# PIC32MK.net
KiCad netlist of a schematic drawn in Altium Designer
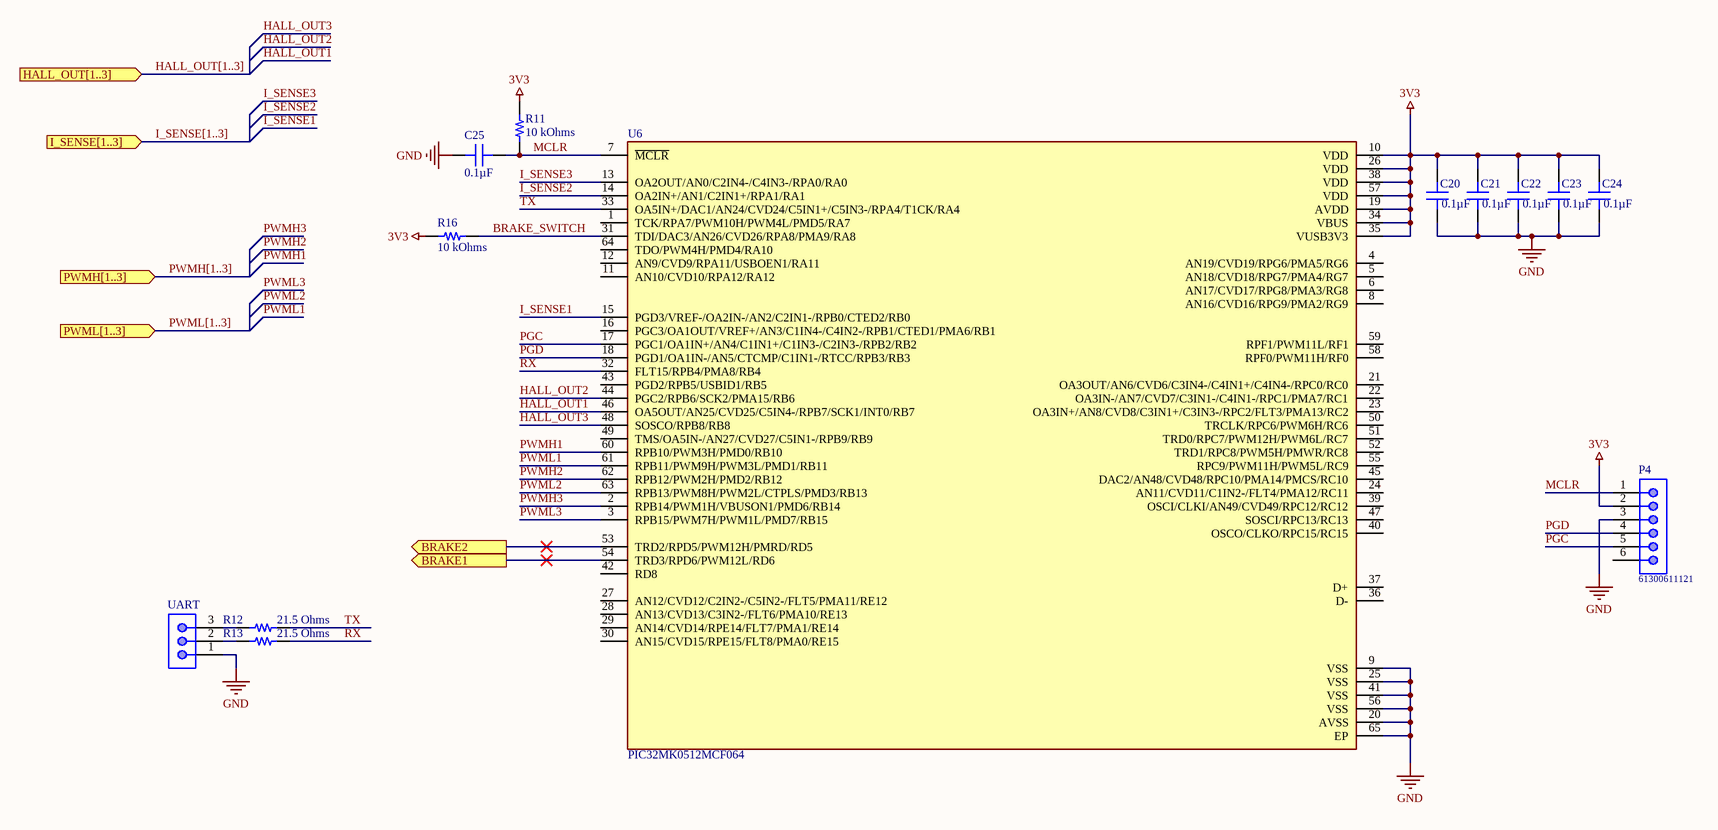
[diagram p0: PIC32MK.SchDoc]

(export (version "E")
  (design (tool "Eeschema 10.0.6"))
  (components
    (comp (ref "C20")
      (value "0.1µF")
      (footprint "CAP 0603_1608")
      (description "CAP CER 0.1UF 100V 0603 EPOXY")
      (fields
        (field (name "PART NUMBER") "GCG188R92A104KA03D")
        (field (name "MANUFACTURER") "Murata Electronics")
      )
      (libsource (lib "Celestial Altium Library - altium_library") (part "Capacitor"))
    )
    (comp (ref "C21")
      (value "0.1µF")
      (footprint "CAP 0603_1608")
      (description "CAP CER 0.1UF 100V 0603 EPOXY")
      (fields
        (field (name "PART NUMBER") "GCG188R92A104KA03D")
        (field (name "MANUFACTURER") "Murata Electronics")
      )
      (libsource (lib "Celestial Altium Library - altium_library") (part "Capacitor"))
    )
    (comp (ref "C22")
      (value "0.1µF")
      (footprint "CAP 0603_1608")
      (description "CAP CER 0.1UF 100V 0603 EPOXY")
      (fields
        (field (name "PART NUMBER") "GCG188R92A104KA03D")
        (field (name "MANUFACTURER") "Murata Electronics")
      )
      (libsource (lib "Celestial Altium Library - altium_library") (part "Capacitor"))
    )
    (comp (ref "C23")
      (value "0.1µF")
      (footprint "CAP 0603_1608")
      (description "CAP CER 0.1UF 100V 0603 EPOXY")
      (fields
        (field (name "PART NUMBER") "GCG188R92A104KA03D")
        (field (name "MANUFACTURER") "Murata Electronics")
      )
      (libsource (lib "Celestial Altium Library - altium_library") (part "Capacitor"))
    )
    (comp (ref "C24")
      (value "0.1µF")
      (footprint "CAP 0603_1608")
      (description "CAP CER 0.1UF 100V 0603 EPOXY")
      (fields
        (field (name "PART NUMBER") "GCG188R92A104KA03D")
        (field (name "MANUFACTURER") "Murata Electronics")
      )
      (libsource (lib "Celestial Altium Library - altium_library") (part "Capacitor"))
    )
    (comp (ref "C25")
      (value "0.1µF")
      (footprint "CAP 0603_1608")
      (description "CAP CER 0.1UF 100V 0603 EPOXY")
      (fields
        (field (name "PART NUMBER") "GCG188R92A104KA03D")
        (field (name "MANUFACTURER") "Murata Electronics")
      )
      (libsource (lib "Celestial Altium Library - altium_library") (part "Capacitor"))
    )
    (comp (ref "P4")
      (value "61300611121")
      (footprint "61300611121")
      (description "WR-PHD Pin Header, THT, pitch 2.54mm, Single Row, Vertical, 6p")
      (fields (field (name "MANUFACTURER") "Wurth Elektronik"))
      (libsource (lib "Altium_WR-PHD") (part "61300611121"))
    )
    (comp (ref "R11")
      (value "10 kOhms")
      (footprint "RES 0603_1608")
      (description "RES 10K OHM 0.1% 1/16W 0603")
      (fields
        (field (name "PART NUMBER") "RNCS0603BKE10K0")
        (field (name "MANUFACTURER") "Stackpole Electronics Inc")
      )
      (libsource (lib "Celestial Altium Library - altium_library") (part "Resistor"))
    )
    (comp (ref "R12")
      (value "21.5 Ohms")
      (footprint "RES 0603_1608")
      (description "RES SMD 21.5 OHM 1% 1/10W 0603")
      (fields
        (field (name "PART NUMBER") "ERJ-3EKF21R5V")
        (field (name "MANUFACTURER") "Panasonic Electronic Components")
      )
      (libsource (lib "Celestial Altium Library - altium_library") (part "Resistor"))
    )
    (comp (ref "R13")
      (value "21.5 Ohms")
      (footprint "RES 0603_1608")
      (description "RES SMD 21.5 OHM 1% 1/10W 0603")
      (fields
        (field (name "PART NUMBER") "ERJ-3EKF21R5V")
        (field (name "MANUFACTURER") "Panasonic Electronic Components")
      )
      (libsource (lib "Celestial Altium Library - altium_library") (part "Resistor"))
    )
    (comp (ref "R16")
      (value "10 kOhms")
      (footprint "RES 0603_1608")
      (description "RES 10K OHM 0.1% 1/16W 0603")
      (fields
        (field (name "PART NUMBER") "RNCS0603BKE10K0")
        (field (name "MANUFACTURER") "Stackpole Electronics Inc")
      )
      (libsource (lib "Celestial Altium Library - altium_library") (part "Resistor"))
    )
    (comp (ref "U6")
      (value "PIC32MK0512MCF064")
      (footprint "QFN50P900X900X100-65N")
      (description "PIC32MK Microcontroller IC 32-Bit 120MHz 1MB _1M x 8_ FLASH 64-TQFP _10x10_")
      (fields
        (field (name "MP") "PIC32MK1024MCF064-I/PT")
        (field (name "DIGI-KEY_PART_NUMBER") "PIC32MK1024MCF064-I/PT-ND")
      )
      (libsource (lib "IC") (part "PIC32MK0512MCF064"))
    )
    (comp (ref "UART")
      (value "3 pin 2mm JST Male")
      (footprint "3pin - 2mm header")
      (libsource (lib "IC") (part "3 pin 2mm JST Male"))
    )
  )
  (nets
    (net (code "1") (name "/BRAKE1") (class "Default")
      (node (ref "U6") (pin "54") (pinfunction "TRD3/RPD6/PWM12L/RD6_54") (pintype "passive"))
    )
    (net (code "2") (name "/BRAKE2") (class "Default")
      (node (ref "U6") (pin "53") (pinfunction "TRD2/RPD5/PWM12H/PMRD/RD5_53") (pintype "passive"))
    )
    (net (code "3") (name "/BRAKE_SWITCH") (class "Default")
      (node (ref "R16") (pin "1") (pinfunction "1_1") (pintype "passive"))
      (node (ref "U6") (pin "31") (pinfunction "TDI/DAC3/AN26/CVD26/RPA8/PMA9/RA8_31") (pintype "passive"))
    )
    (net (code "4") (name "/HALL_OUT1") (class "Default")
      (node (ref "U6") (pin "46") (pinfunction "OA5OUT/AN25/CVD25/C5IN4-/RPB7/SCK1/INT0/RB7_46") (pintype "passive"))
    )
    (net (code "5") (name "/HALL_OUT2") (class "Default")
      (node (ref "U6") (pin "44") (pinfunction "PGC2/RPB6/SCK2/PMA15/RB6_44") (pintype "passive"))
    )
    (net (code "6") (name "/HALL_OUT3") (class "Default")
      (node (ref "U6") (pin "48") (pinfunction "SOSCO/RPB8/RB8_48") (pintype "passive"))
    )
    (net (code "8") (name "/I_SENSE1") (class "Default")
      (node (ref "U6") (pin "15") (pinfunction "PGD3/VREF-/OA2IN-/AN2/C2IN1-/RPB0/CTED2/RB0_15") (pintype "passive"))
    )
    (net (code "9") (name "/I_SENSE2") (class "Default")
      (node (ref "U6") (pin "14") (pinfunction "OA2IN+/AN1/C2IN1+/RPA1/RA1_14") (pintype "passive"))
    )
    (net (code "10") (name "/I_SENSE3") (class "Default")
      (node (ref "U6") (pin "13") (pinfunction "OA2OUT/AN0/C2IN4-/C4IN3-/RPA0/RA0_13") (pintype "passive"))
    )
    (net (code "12") (name "/MCLR") (class "Default")
      (node (ref "C25") (pin "1") (pinfunction "1_1") (pintype "passive"))
      (node (ref "P4") (pin "1") (pinfunction "1_1") (pintype "passive"))
      (node (ref "R11") (pin "1") (pinfunction "1_1") (pintype "passive"))
      (node (ref "U6") (pin "7") (pinfunction "~{MCLR}_7") (pintype "passive"))
    )
    (net (code "13") (name "/PGC") (class "Default")
      (node (ref "P4") (pin "5") (pinfunction "5_5") (pintype "passive"))
      (node (ref "U6") (pin "17") (pinfunction "PGC1/OA1IN+/AN4/C1IN1+/C1IN3-/C2IN3-/RPB2/RB2_17") (pintype "passive"))
    )
    (net (code "14") (name "/PGD") (class "Default")
      (node (ref "P4") (pin "4") (pinfunction "4_4") (pintype "passive"))
      (node (ref "U6") (pin "18") (pinfunction "PGD1/OA1IN-/AN5/CTCMP/C1IN1-/RTCC/RPB3/RB3_18") (pintype "passive"))
    )
    (net (code "15") (name "/PWMH1") (class "Default")
      (node (ref "U6") (pin "60") (pinfunction "RPB10/PWM3H/PMD0/RB10_60") (pintype "passive"))
    )
    (net (code "16") (name "/PWMH2") (class "Default")
      (node (ref "U6") (pin "62") (pinfunction "RPB12/PWM2H/PMD2/RB12_62") (pintype "passive"))
    )
    (net (code "17") (name "/PWMH3") (class "Default")
      (node (ref "U6") (pin "2") (pinfunction "RPB14/PWM1H/VBUSON1/PMD6/RB14_2") (pintype "passive"))
    )
    (net (code "19") (name "/PWML1") (class "Default")
      (node (ref "U6") (pin "61") (pinfunction "RPB11/PWM9H/PWM3L/PMD1/RB11_61") (pintype "passive"))
    )
    (net (code "20") (name "/PWML2") (class "Default")
      (node (ref "U6") (pin "63") (pinfunction "RPB13/PWM8H/PWM2L/CTPLS/PMD3/RB13_63") (pintype "passive"))
    )
    (net (code "21") (name "/PWML3") (class "Default")
      (node (ref "U6") (pin "3") (pinfunction "RPB15/PWM7H/PWM1L/PMD7/RB15_3") (pintype "passive"))
    )
    (net (code "23") (name "/RX") (class "Default")
      (node (ref "R13") (pin "2") (pinfunction "2_2") (pintype "passive"))
      (node (ref "U6") (pin "32") (pinfunction "FLT15/RPB4/PMA8/RB4_32") (pintype "passive"))
    )
    (net (code "24") (name "/TX") (class "Default")
      (node (ref "R12") (pin "2") (pinfunction "2_2") (pintype "passive"))
      (node (ref "U6") (pin "33") (pinfunction "OA5IN+/DAC1/AN24/CVD24/C5IN1+/C5IN3-/RPA4/T1CK/RA4_33") (pintype "passive"))
    )
    (net (code "25") (name "3V3") (class "Default")
      (node (ref "C20") (pin "1") (pinfunction "1_1") (pintype "passive"))
      (node (ref "C21") (pin "1") (pinfunction "1_1") (pintype "passive"))
      (node (ref "C22") (pin "1") (pinfunction "1_1") (pintype "passive"))
      (node (ref "C23") (pin "1") (pinfunction "1_1") (pintype "passive"))
      (node (ref "C24") (pin "1") (pinfunction "1_1") (pintype "passive"))
      (node (ref "P4") (pin "2") (pinfunction "2_2") (pintype "passive"))
      (node (ref "R11") (pin "2") (pinfunction "2_2") (pintype "passive"))
      (node (ref "R16") (pin "2") (pinfunction "2_2") (pintype "passive"))
      (node (ref "U6") (pin "10") (pinfunction "VDD_10") (pintype "power_in"))
      (node (ref "U6") (pin "19") (pinfunction "AVDD_19") (pintype "power_in"))
      (node (ref "U6") (pin "26") (pinfunction "VDD_26") (pintype "power_in"))
      (node (ref "U6") (pin "34") (pinfunction "VBUS_34") (pintype "power_in"))
      (node (ref "U6") (pin "35") (pinfunction "VUSB3V3_35") (pintype "passive"))
      (node (ref "U6") (pin "38") (pinfunction "VDD_38") (pintype "power_in"))
      (node (ref "U6") (pin "57") (pinfunction "VDD_57") (pintype "power_in"))
    )
    (net (code "26") (name "GND") (class "Default")
      (node (ref "C20") (pin "2") (pinfunction "2_2") (pintype "passive"))
      (node (ref "C21") (pin "2") (pinfunction "2_2") (pintype "passive"))
      (node (ref "C22") (pin "2") (pinfunction "2_2") (pintype "passive"))
      (node (ref "C23") (pin "2") (pinfunction "2_2") (pintype "passive"))
      (node (ref "C24") (pin "2") (pinfunction "2_2") (pintype "passive"))
      (node (ref "C25") (pin "2") (pinfunction "2_2") (pintype "passive"))
      (node (ref "P4") (pin "3") (pinfunction "3_3") (pintype "passive"))
      (node (ref "U6") (pin "20") (pinfunction "AVSS_20") (pintype "power_in"))
      (node (ref "U6") (pin "25") (pinfunction "VSS_25") (pintype "power_in"))
      (node (ref "U6") (pin "41") (pinfunction "VSS_41") (pintype "power_in"))
      (node (ref "U6") (pin "56") (pinfunction "VSS_56") (pintype "power_in"))
      (node (ref "U6") (pin "65") (pinfunction "EP_65") (pintype "power_in"))
      (node (ref "U6") (pin "9") (pinfunction "VSS_9") (pintype "power_in"))
      (node (ref "UART") (pin "1") (pinfunction "1_1") (pintype "passive"))
    )
    (net (code "27") (name "Net-(R12-Pad1)") (class "Default")
      (node (ref "R12") (pin "1") (pinfunction "1_1") (pintype "passive"))
      (node (ref "UART") (pin "3") (pinfunction "3_3") (pintype "passive"))
    )
    (net (code "28") (name "Net-(R13-Pad1)") (class "Default")
      (node (ref "R13") (pin "1") (pinfunction "1_1") (pintype "passive"))
      (node (ref "UART") (pin "2") (pinfunction "2_2") (pintype "passive"))
    )
    (net (code "29") (name "unconnected-(P4-Pad6)") (class "Default")
      (node (ref "P4") (pin "6") (pinfunction "6_6") (pintype "passive"))
    )
    (net (code "30") (name "unconnected-(U6-AN9{slash}CVD9{slash}RPA11{slash}USBOEN1{slash}RA11-Pad12)") (class "Default")
      (node (ref "U6") (pin "12") (pinfunction "AN9/CVD9/RPA11/USBOEN1/RA11_12") (pintype "passive"))
    )
    (net (code "31") (name "unconnected-(U6-AN10{slash}CVD10{slash}RPA12{slash}RA12-Pad11)") (class "Default")
      (node (ref "U6") (pin "11") (pinfunction "AN10/CVD10/RPA12/RA12_11") (pintype "passive"))
    )
    (net (code "32") (name "unconnected-(U6-AN11{slash}CVD11{slash}C1IN2-{slash}FLT4{slash}PMA12{slash}RC11-Pad24)") (class "Default")
      (node (ref "U6") (pin "24") (pinfunction "AN11/CVD11/C1IN2-/FLT4/PMA12/RC11_24") (pintype "passive"))
    )
    (net (code "33") (name "unconnected-(U6-AN12{slash}CVD12{slash}C2IN2-{slash}C5IN2-{slash}FLT5{slash}PMA11{slash}RE12-Pad27)") (class "Default")
      (node (ref "U6") (pin "27") (pinfunction "AN12/CVD12/C2IN2-/C5IN2-/FLT5/PMA11/RE12_27") (pintype "passive"))
    )
    (net (code "34") (name "unconnected-(U6-AN13{slash}CVD13{slash}C3IN2-{slash}FLT6{slash}PMA10{slash}RE13-Pad28)") (class "Default")
      (node (ref "U6") (pin "28") (pinfunction "AN13/CVD13/C3IN2-/FLT6/PMA10/RE13_28") (pintype "passive"))
    )
    (net (code "35") (name "unconnected-(U6-AN14{slash}CVD14{slash}RPE14{slash}FLT7{slash}PMA1{slash}RE14-Pad29)") (class "Default")
      (node (ref "U6") (pin "29") (pinfunction "AN14/CVD14/RPE14/FLT7/PMA1/RE14_29") (pintype "passive"))
    )
    (net (code "36") (name "unconnected-(U6-AN15{slash}CVD15{slash}RPE15{slash}FLT8{slash}PMA0{slash}RE15-Pad30)") (class "Default")
      (node (ref "U6") (pin "30") (pinfunction "AN15/CVD15/RPE15/FLT8/PMA0/RE15_30") (pintype "passive"))
    )
    (net (code "37") (name "unconnected-(U6-AN16{slash}CVD16{slash}RPG9{slash}PMA2{slash}RG9-Pad8)") (class "Default")
      (node (ref "U6") (pin "8") (pinfunction "AN16/CVD16/RPG9/PMA2/RG9_8") (pintype "passive"))
    )
    (net (code "38") (name "unconnected-(U6-AN17{slash}CVD17{slash}RPG8{slash}PMA3{slash}RG8-Pad6)") (class "Default")
      (node (ref "U6") (pin "6") (pinfunction "AN17/CVD17/RPG8/PMA3/RG8_6") (pintype "passive"))
    )
    (net (code "39") (name "unconnected-(U6-AN18{slash}CVD18{slash}RPG7{slash}PMA4{slash}RG7-Pad5)") (class "Default")
      (node (ref "U6") (pin "5") (pinfunction "AN18/CVD18/RPG7/PMA4/RG7_5") (pintype "passive"))
    )
    (net (code "40") (name "unconnected-(U6-AN19{slash}CVD19{slash}RPG6{slash}PMA5{slash}RG6-Pad4)") (class "Default")
      (node (ref "U6") (pin "4") (pinfunction "AN19/CVD19/RPG6/PMA5/RG6_4") (pintype "passive"))
    )
    (net (code "41") (name "unconnected-(U6-D+-Pad37)") (class "Default")
      (node (ref "U6") (pin "37") (pinfunction "D+_37") (pintype "passive"))
    )
    (net (code "42") (name "unconnected-(U6-D--Pad36)") (class "Default")
      (node (ref "U6") (pin "36") (pinfunction "D-_36") (pintype "passive"))
    )
    (net (code "43") (name "unconnected-(U6-DAC2{slash}AN48{slash}CVD48{slash}RPC10{slash}PMA14{slash}PMCS{slash}RC10-Pad45)") (class "Default")
      (node (ref "U6") (pin "45") (pinfunction "DAC2/AN48/CVD48/RPC10/PMA14/PMCS/RC10_45") (pintype "passive"))
    )
    (net (code "44") (name "unconnected-(U6-OA3IN+{slash}AN8{slash}CVD8{slash}C3IN1+{slash}C3IN3-{slash}RPC2{slash}FLT3{slash}PMA13{slash}RC2-Pad23)") (class "Default")
      (node (ref "U6") (pin "23") (pinfunction "OA3IN+/AN8/CVD8/C3IN1+/C3IN3-/RPC2/FLT3/PMA13/RC2_23") (pintype "passive"))
    )
    (net (code "45") (name "unconnected-(U6-OA3IN-{slash}AN7{slash}CVD7{slash}C3IN1-{slash}C4IN1-{slash}RPC1{slash}PMA7{slash}RC1-Pad22)") (class "Default")
      (node (ref "U6") (pin "22") (pinfunction "OA3IN-/AN7/CVD7/C3IN1-/C4IN1-/RPC1/PMA7/RC1_22") (pintype "passive"))
    )
    (net (code "46") (name "unconnected-(U6-OA3OUT{slash}AN6{slash}CVD6{slash}C3IN4-{slash}C4IN1+{slash}C4IN4-{slash}RPC0{slash}RC0-Pad21)") (class "Default")
      (node (ref "U6") (pin "21") (pinfunction "OA3OUT/AN6/CVD6/C3IN4-/C4IN1+/C4IN4-/RPC0/RC0_21") (pintype "passive"))
    )
    (net (code "47") (name "unconnected-(U6-OSCI{slash}CLKI{slash}AN49{slash}CVD49{slash}RPC12{slash}RC12-Pad39)") (class "Default")
      (node (ref "U6") (pin "39") (pinfunction "OSCI/CLKI/AN49/CVD49/RPC12/RC12_39") (pintype "passive"))
    )
    (net (code "48") (name "unconnected-(U6-OSCO{slash}CLKO{slash}RPC15{slash}RC15-Pad40)") (class "Default")
      (node (ref "U6") (pin "40") (pinfunction "OSCO/CLKO/RPC15/RC15_40") (pintype "passive"))
    )
    (net (code "49") (name "unconnected-(U6-PGC3{slash}OA1OUT{slash}VREF+{slash}AN3{slash}C1IN4-{slash}C4IN2-{slash}RPB1{slash}CTED1{slash}PMA6{slash}RB1-Pad16)") (class "Default")
      (node (ref "U6") (pin "16") (pinfunction "PGC3/OA1OUT/VREF+/AN3/C1IN4-/C4IN2-/RPB1/CTED1/PMA6/RB1_16") (pintype "passive"))
    )
    (net (code "50") (name "unconnected-(U6-PGD2{slash}RPB5{slash}USBID1{slash}RB5-Pad43)") (class "Default")
      (node (ref "U6") (pin "43") (pinfunction "PGD2/RPB5/USBID1/RB5_43") (pintype "passive"))
    )
    (net (code "51") (name "unconnected-(U6-RD8-Pad42)") (class "Default")
      (node (ref "U6") (pin "42") (pinfunction "RD8_42") (pintype "passive"))
    )
    (net (code "52") (name "unconnected-(U6-RPC9{slash}PWM11H{slash}PWM5L{slash}RC9-Pad55)") (class "Default")
      (node (ref "U6") (pin "55") (pinfunction "RPC9/PWM11H/PWM5L/RC9_55") (pintype "passive"))
    )
    (net (code "53") (name "unconnected-(U6-RPF0{slash}PWM11H{slash}RF0-Pad58)") (class "Default")
      (node (ref "U6") (pin "58") (pinfunction "RPF0/PWM11H/RF0_58") (pintype "passive"))
    )
    (net (code "54") (name "unconnected-(U6-RPF1{slash}PWM11L{slash}RF1-Pad59)") (class "Default")
      (node (ref "U6") (pin "59") (pinfunction "RPF1/PWM11L/RF1_59") (pintype "passive"))
    )
    (net (code "55") (name "unconnected-(U6-SOSCI{slash}RPC13{slash}RC13-Pad47)") (class "Default")
      (node (ref "U6") (pin "47") (pinfunction "SOSCI/RPC13/RC13_47") (pintype "passive"))
    )
    (net (code "56") (name "unconnected-(U6-TCK{slash}RPA7{slash}PWM10H{slash}PWM4L{slash}PMD5{slash}RA7-Pad1)") (class "Default")
      (node (ref "U6") (pin "1") (pinfunction "TCK/RPA7/PWM10H/PWM4L/PMD5/RA7_1") (pintype "passive"))
    )
    (net (code "57") (name "unconnected-(U6-TDO{slash}PWM4H{slash}PMD4{slash}RA10-Pad64)") (class "Default")
      (node (ref "U6") (pin "64") (pinfunction "TDO/PWM4H/PMD4/RA10_64") (pintype "passive"))
    )
    (net (code "58") (name "unconnected-(U6-TMS{slash}OA5IN-{slash}AN27{slash}CVD27{slash}C5IN1-{slash}RPB9{slash}RB9-Pad49)") (class "Default")
      (node (ref "U6") (pin "49") (pinfunction "TMS/OA5IN-/AN27/CVD27/C5IN1-/RPB9/RB9_49") (pintype "passive"))
    )
    (net (code "59") (name "unconnected-(U6-TRCLK{slash}RPC6{slash}PWM6H{slash}RC6-Pad50)") (class "Default")
      (node (ref "U6") (pin "50") (pinfunction "TRCLK/RPC6/PWM6H/RC6_50") (pintype "passive"))
    )
    (net (code "60") (name "unconnected-(U6-TRD0{slash}RPC7{slash}PWM12H{slash}PWM6L{slash}RC7-Pad51)") (class "Default")
      (node (ref "U6") (pin "51") (pinfunction "TRD0/RPC7/PWM12H/PWM6L/RC7_51") (pintype "passive"))
    )
    (net (code "61") (name "unconnected-(U6-TRD1{slash}RPC8{slash}PWM5H{slash}PMWR{slash}RC8-Pad52)") (class "Default")
      (node (ref "U6") (pin "52") (pinfunction "TRD1/RPC8/PWM5H/PMWR/RC8_52") (pintype "passive"))
    )
  )
)
